# Whitespace_Daughtercard_connector.net
KiCad netlist of a schematic drawn in Altium Designer
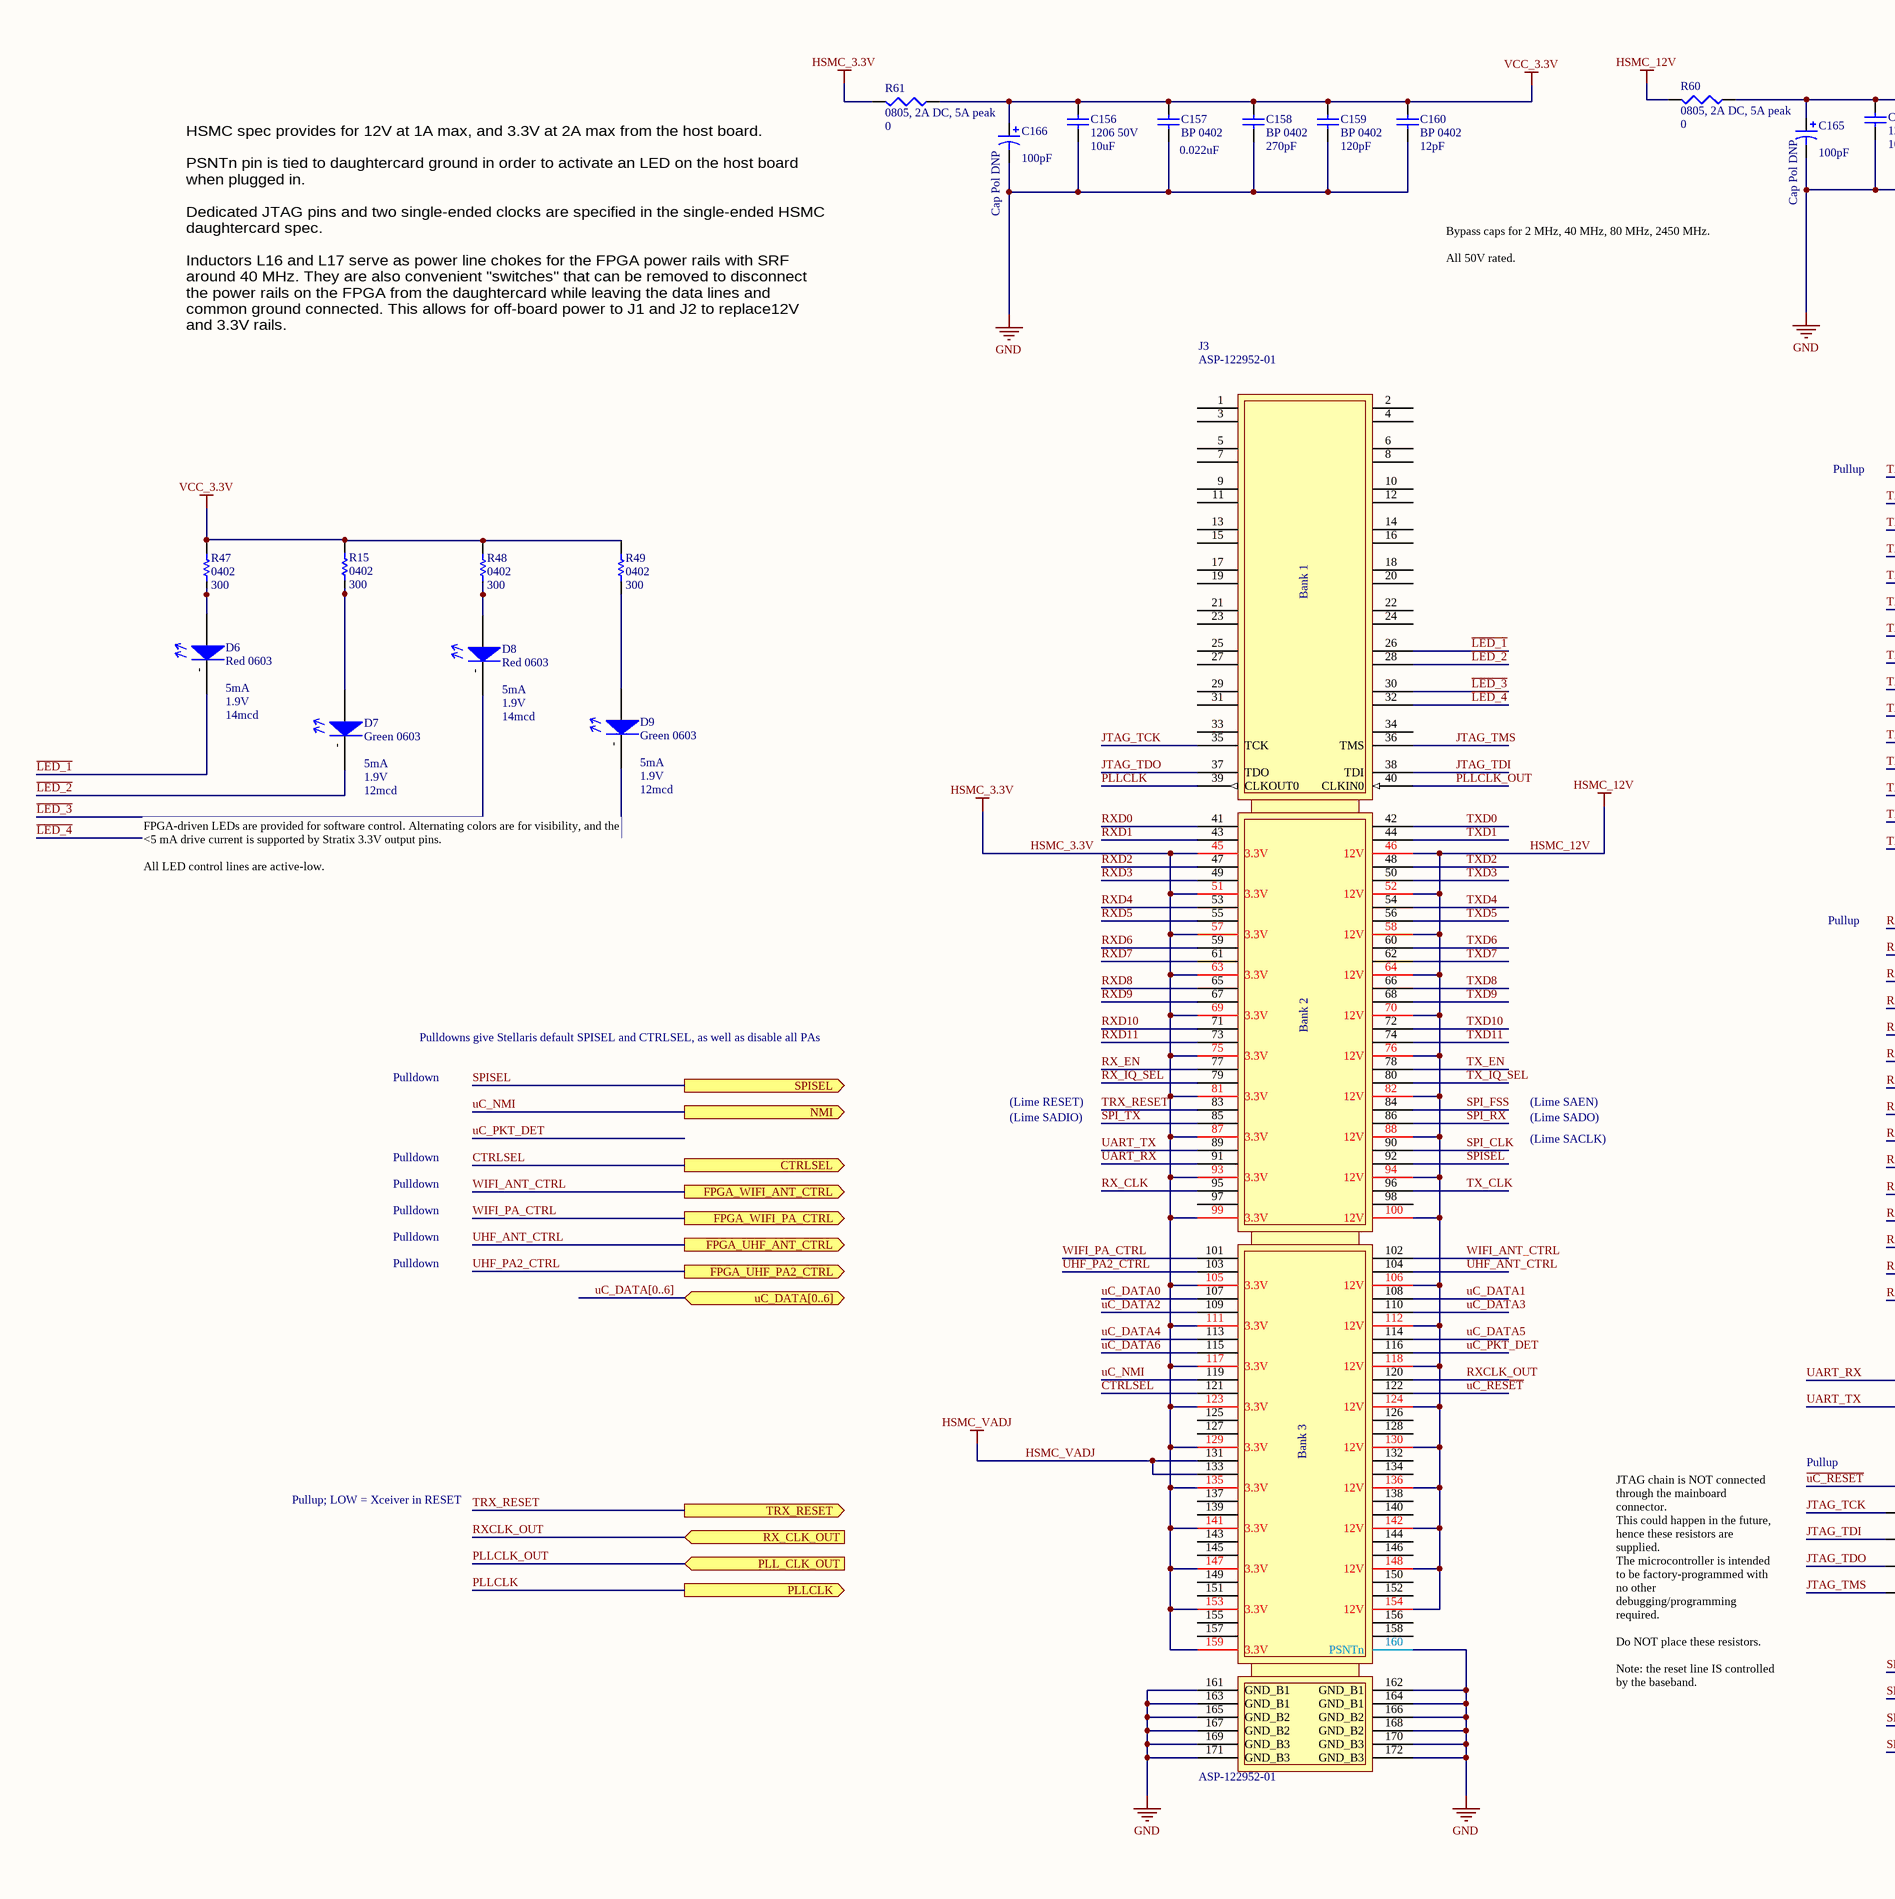
[diagram p0: Whitespace_Daughtercard_connector.SchDoc, left]
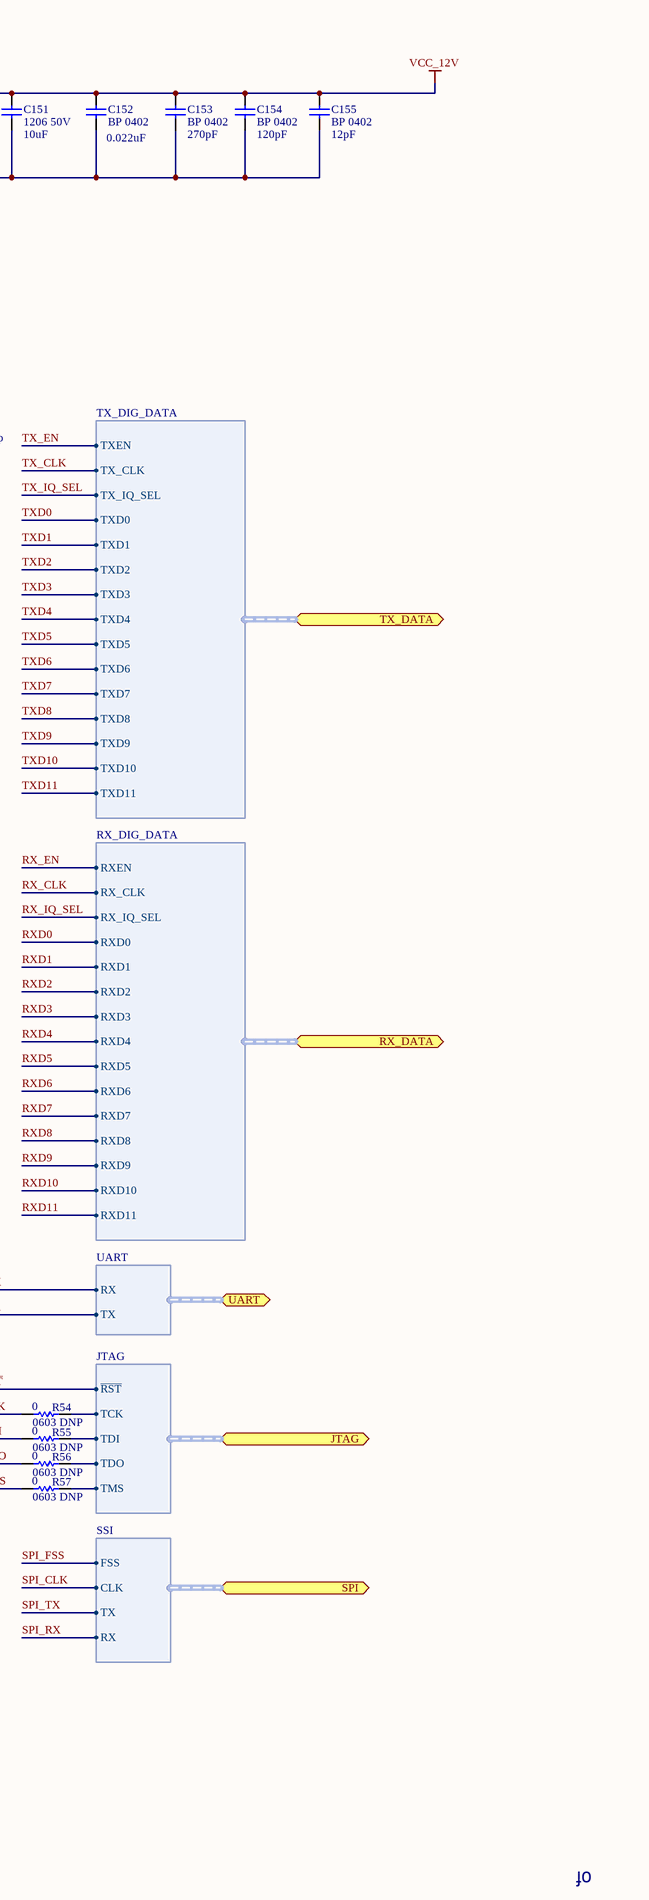
[diagram p1: Whitespace_Daughtercard_connector.SchDoc, right]

(export (version "E")
  (design (tool "Eeschema 10.0.6"))
  (components
    (comp (ref "C151")
      (value "1206 50V")
      (footprint "1206_SMT_v3")
      (description "Capacitor")
      (fields (field (name "ALTIUM_VALUE") "10uF") (field (name "PUBLISHER") "Altium Limited"))
      (libsource (lib "Miscellaneous Devices") (part "Cap"))
    )
    (comp (ref "C152")
      (value "BP 0402")
      (footprint "0402_SMT_V3")
      (description "Capacitor")
      (fields (field (name "ALTIUM_VALUE") "0.022uF") (field (name "PUBLISHER") "Altium Limited"))
      (libsource (lib "Miscellaneous Devices") (part "Cap"))
    )
    (comp (ref "C153")
      (value "BP 0402")
      (footprint "0402_SMT_v3")
      (description "Capacitor")
      (fields (field (name "ALTIUM_VALUE") "270pF") (field (name "PUBLISHER") "Altium Limited"))
      (libsource (lib "Miscellaneous Devices") (part "Cap"))
    )
    (comp (ref "C154")
      (value "BP 0402")
      (footprint "0402_SMT_v3")
      (description "Capacitor")
      (fields (field (name "ALTIUM_VALUE") "120pF") (field (name "PUBLISHER") "Altium Limited"))
      (libsource (lib "Miscellaneous Devices") (part "Cap"))
    )
    (comp (ref "C155")
      (value "BP 0402")
      (footprint "0402_SMT_v3")
      (description "Capacitor")
      (fields (field (name "ALTIUM_VALUE") "12pF") (field (name "PUBLISHER") "Altium Limited"))
      (libsource (lib "Miscellaneous Devices") (part "Cap"))
    )
    (comp (ref "C156")
      (value "1206 50V")
      (footprint "1206_SMT_v3")
      (description "Capacitor")
      (fields (field (name "ALTIUM_VALUE") "10uF") (field (name "PUBLISHER") "Altium Limited"))
      (libsource (lib "Miscellaneous Devices") (part "Cap"))
    )
    (comp (ref "C157")
      (value "BP 0402")
      (footprint "0402_SMT_V3")
      (description "Capacitor")
      (fields (field (name "ALTIUM_VALUE") "0.022uF") (field (name "PUBLISHER") "Altium Limited"))
      (libsource (lib "Miscellaneous Devices") (part "Cap"))
    )
    (comp (ref "C158")
      (value "BP 0402")
      (footprint "0402_SMT_v3")
      (description "Capacitor")
      (fields (field (name "ALTIUM_VALUE") "270pF") (field (name "PUBLISHER") "Altium Limited"))
      (libsource (lib "Miscellaneous Devices") (part "Cap"))
    )
    (comp (ref "C159")
      (value "BP 0402")
      (footprint "0402_SMT_v3")
      (description "Capacitor")
      (fields (field (name "ALTIUM_VALUE") "120pF") (field (name "PUBLISHER") "Altium Limited"))
      (libsource (lib "Miscellaneous Devices") (part "Cap"))
    )
    (comp (ref "C160")
      (value "BP 0402")
      (footprint "0402_SMT_v3")
      (description "Capacitor")
      (fields (field (name "ALTIUM_VALUE") "12pF") (field (name "PUBLISHER") "Altium Limited"))
      (libsource (lib "Miscellaneous Devices") (part "Cap"))
    )
    (comp (ref "C165")
      (value "Cap Pol DNP")
      (footprint "PANASONIC_ELEC_CAP_G_v2")
      (description "Polarized Capacitor (Surface Mount)")
      (fields (field (name "ALTIUM_VALUE") "100pF") (field (name "PUBLISHER") "Altium Limited"))
      (libsource (lib "Miscellaneous Devices") (part "Cap Pol3"))
    )
    (comp (ref "C166")
      (value "Cap Pol DNP")
      (footprint "PANASONIC_ELEC_CAP_G_v2")
      (description "Polarized Capacitor (Surface Mount)")
      (fields (field (name "ALTIUM_VALUE") "100pF") (field (name "PUBLISHER") "Altium Limited"))
      (libsource (lib "Miscellaneous Devices") (part "Cap Pol3"))
    )
    (comp (ref "D6")
      (value "Red 0603")
      (footprint "0603_POLAR")
      (fields
        (field (name "CURRENT") "5mA")
        (field (name "FORWARD VOLTAGE DROP") "1.9V")
        (field (name "LUMINOSITY") "14mcd")
      )
      (libsource (lib "RNG_Parts") (part "LED"))
    )
    (comp (ref "D7")
      (value "Green 0603")
      (footprint "0603_POLAR")
      (fields
        (field (name "CURRENT") "5mA")
        (field (name "FORWARD VOLTAGE") "1.9V")
        (field (name "LUMINOSITY") "12mcd")
      )
      (libsource (lib "RNG_Parts") (part "LED"))
    )
    (comp (ref "D8")
      (value "Red 0603")
      (footprint "0603_POLAR")
      (fields
        (field (name "CURRENT") "5mA")
        (field (name "FORWARD VOLTAGE DROP") "1.9V")
        (field (name "LUMINOSITY") "14mcd")
      )
      (libsource (lib "RNG_Parts") (part "LED"))
    )
    (comp (ref "D9")
      (value "Green 0603")
      (footprint "0603_POLAR")
      (fields
        (field (name "CURRENT") "5mA")
        (field (name "FORWARD VOLTAGE") "1.9V")
        (field (name "LUMINOSITY") "12mcd")
      )
      (libsource (lib "RNG_Parts") (part "LED"))
    )
    (comp (ref "J3")
      (value "ASP-122952-01")
      (footprint "ASP-122952-01")
      (description "Samtec HSMC Daughtercard Connector (Male)")
      (libsource (lib "RNG_Parts") (part "ASP-122952-01"))
    )
    (comp (ref "R15")
      (value "0402")
      (footprint "0402_SMT_v3")
      (description "Semiconductor Resistor")
      (fields (field (name "ALTIUM_VALUE") "300") (field (name "PUBLISHER") "Altium Limited"))
      (libsource (lib "Miscellaneous Devices") (part "Res Semi"))
    )
    (comp (ref "R47")
      (value "0402")
      (footprint "0402_SMT_v3")
      (description "Semiconductor Resistor")
      (fields (field (name "ALTIUM_VALUE") "300") (field (name "PUBLISHER") "Altium Limited"))
      (libsource (lib "Miscellaneous Devices") (part "Res Semi"))
    )
    (comp (ref "R48")
      (value "0402")
      (footprint "0402_SMT_v3")
      (description "Semiconductor Resistor")
      (fields (field (name "ALTIUM_VALUE") "300") (field (name "PUBLISHER") "Altium Limited"))
      (libsource (lib "Miscellaneous Devices") (part "Res Semi"))
    )
    (comp (ref "R49")
      (value "0402")
      (footprint "0402_SMT_v3")
      (description "Semiconductor Resistor")
      (fields (field (name "ALTIUM_VALUE") "300") (field (name "PUBLISHER") "Altium Limited"))
      (libsource (lib "Miscellaneous Devices") (part "Res Semi"))
    )
    (comp (ref "R54")
      (value "0603 DNP")
      (footprint "0603_SMT_v3")
      (description "Semiconductor Resistor")
      (fields (field (name "ALTIUM_VALUE") "0") (field (name "PUBLISHER") "Altium Limited"))
      (libsource (lib "Miscellaneous Devices") (part "Res Semi"))
    )
    (comp (ref "R55")
      (value "0603 DNP")
      (footprint "0603_SMT_v3")
      (description "Semiconductor Resistor")
      (fields (field (name "ALTIUM_VALUE") "0") (field (name "PUBLISHER") "Altium Limited"))
      (libsource (lib "Miscellaneous Devices") (part "Res Semi"))
    )
    (comp (ref "R56")
      (value "0603 DNP")
      (footprint "0603_SMT_v3")
      (description "Semiconductor Resistor")
      (fields (field (name "ALTIUM_VALUE") "0") (field (name "PUBLISHER") "Altium Limited"))
      (libsource (lib "Miscellaneous Devices") (part "Res Semi"))
    )
    (comp (ref "R57")
      (value "0603 DNP")
      (footprint "0603_SMT_v3")
      (description "Semiconductor Resistor")
      (fields (field (name "ALTIUM_VALUE") "0") (field (name "PUBLISHER") "Altium Limited"))
      (libsource (lib "Miscellaneous Devices") (part "Res Semi"))
    )
    (comp (ref "R60")
      (value "0805, 2A DC, 5A peak")
      (footprint "0805_SMT_v3")
      (description "Resistor")
      (fields (field (name "ALTIUM_VALUE") "0") (field (name "PUBLISHER") "Altium Limited"))
      (libsource (lib "Miscellaneous Devices") (part "Res3"))
    )
    (comp (ref "R61")
      (value "0805, 2A DC, 5A peak")
      (footprint "0805_SMT_v3")
      (description "Resistor")
      (fields (field (name "ALTIUM_VALUE") "0") (field (name "PUBLISHER") "Altium Limited"))
      (libsource (lib "Miscellaneous Devices") (part "Res3"))
    )
  )
  (nets
    (net (code "6") (name "/CTRLSEL") (class "Default")
      (node (ref "J3") (pin "121") (pinfunction "121_121") (pintype "passive"))
    )
    (net (code "7") (name "/JTAG_TCK") (class "Default")
      (node (ref "J3") (pin "35") (pinfunction "TCK_35") (pintype "passive"))
      (node (ref "R54") (pin "2") (pinfunction "2_2") (pintype "passive"))
    )
    (net (code "8") (name "/JTAG_TDI") (class "Default")
      (node (ref "J3") (pin "38") (pinfunction "TDI_38") (pintype "passive"))
      (node (ref "R55") (pin "2") (pinfunction "2_2") (pintype "passive"))
    )
    (net (code "9") (name "/JTAG_TDO") (class "Default")
      (node (ref "J3") (pin "37") (pinfunction "TDO_37") (pintype "passive"))
      (node (ref "R56") (pin "2") (pinfunction "2_2") (pintype "passive"))
    )
    (net (code "10") (name "/JTAG_TMS") (class "Default")
      (node (ref "J3") (pin "36") (pinfunction "TMS_36") (pintype "passive"))
      (node (ref "R57") (pin "2") (pinfunction "2_2") (pintype "passive"))
    )
    (net (code "11") (name "/LED_1") (class "Default")
      (node (ref "D6") (pin "-") (pinfunction "Cathode_-") (pintype "power_in"))
      (node (ref "J3") (pin "26") (pinfunction "26_26") (pintype "passive"))
    )
    (net (code "12") (name "/LED_2") (class "Default")
      (node (ref "D7") (pin "-") (pinfunction "Cathode_-") (pintype "power_in"))
      (node (ref "J3") (pin "28") (pinfunction "28_28") (pintype "passive"))
    )
    (net (code "13") (name "/LED_3") (class "Default")
      (node (ref "D8") (pin "-") (pinfunction "Cathode_-") (pintype "power_in"))
      (node (ref "J3") (pin "30") (pinfunction "30_30") (pintype "passive"))
    )
    (net (code "14") (name "/LED_4") (class "Default")
      (node (ref "D9") (pin "-") (pinfunction "Cathode_-") (pintype "power_in"))
      (node (ref "J3") (pin "32") (pinfunction "32_32") (pintype "passive"))
    )
    (net (code "15") (name "/PLLCLK") (class "Default")
      (node (ref "J3") (pin "39") (pinfunction "CLKOUT0_39") (pintype "output"))
    )
    (net (code "16") (name "/PLLCLK_OUT") (class "Default")
      (node (ref "J3") (pin "40") (pinfunction "CLKIN0_40") (pintype "input"))
    )
    (net (code "17") (name "/RXCLK_OUT") (class "Default")
      (node (ref "J3") (pin "120") (pinfunction "120_120") (pintype "passive"))
    )
    (net (code "18") (name "/RXD0") (class "Default")
      (node (ref "J3") (pin "41") (pinfunction "41_41") (pintype "passive"))
    )
    (net (code "19") (name "/RXD1") (class "Default")
      (node (ref "J3") (pin "43") (pinfunction "43_43") (pintype "passive"))
    )
    (net (code "20") (name "/RXD2") (class "Default")
      (node (ref "J3") (pin "47") (pinfunction "47_47") (pintype "passive"))
    )
    (net (code "21") (name "/RXD3") (class "Default")
      (node (ref "J3") (pin "49") (pinfunction "49_49") (pintype "passive"))
    )
    (net (code "22") (name "/RXD4") (class "Default")
      (node (ref "J3") (pin "53") (pinfunction "53_53") (pintype "passive"))
    )
    (net (code "23") (name "/RXD5") (class "Default")
      (node (ref "J3") (pin "55") (pinfunction "55_55") (pintype "passive"))
    )
    (net (code "24") (name "/RXD6") (class "Default")
      (node (ref "J3") (pin "59") (pinfunction "59_59") (pintype "passive"))
    )
    (net (code "25") (name "/RXD7") (class "Default")
      (node (ref "J3") (pin "61") (pinfunction "61_61") (pintype "passive"))
    )
    (net (code "26") (name "/RXD8") (class "Default")
      (node (ref "J3") (pin "65") (pinfunction "65_65") (pintype "passive"))
    )
    (net (code "27") (name "/RXD9") (class "Default")
      (node (ref "J3") (pin "67") (pinfunction "67_67") (pintype "passive"))
    )
    (net (code "28") (name "/RXD10") (class "Default")
      (node (ref "J3") (pin "71") (pinfunction "71_71") (pintype "passive"))
    )
    (net (code "29") (name "/RXD11") (class "Default")
      (node (ref "J3") (pin "73") (pinfunction "73_73") (pintype "passive"))
    )
    (net (code "30") (name "/RX_CLK") (class "Default")
      (node (ref "J3") (pin "95") (pinfunction "95_95") (pintype "passive"))
    )
    (net (code "31") (name "/RX_EN") (class "Default")
      (node (ref "J3") (pin "77") (pinfunction "77_77") (pintype "passive"))
    )
    (net (code "32") (name "/RX_IQ_SEL") (class "Default")
      (node (ref "J3") (pin "79") (pinfunction "79_79") (pintype "passive"))
    )
    (net (code "33") (name "/SPISEL") (class "Default")
      (node (ref "J3") (pin "92") (pinfunction "92_92") (pintype "passive"))
    )
    (net (code "34") (name "/SPI_CLK") (class "Default")
      (node (ref "J3") (pin "90") (pinfunction "90_90") (pintype "passive"))
    )
    (net (code "35") (name "/SPI_FSS") (class "Default")
      (node (ref "J3") (pin "84") (pinfunction "84_84") (pintype "passive"))
    )
    (net (code "36") (name "/SPI_RX") (class "Default")
      (node (ref "J3") (pin "86") (pinfunction "86_86") (pintype "passive"))
    )
    (net (code "37") (name "/SPI_TX") (class "Default")
      (node (ref "J3") (pin "85") (pinfunction "85_85") (pintype "passive"))
    )
    (net (code "38") (name "/TCK") (class "Default")
      (node (ref "R54") (pin "1") (pinfunction "1_1") (pintype "passive"))
    )
    (net (code "39") (name "/TDI") (class "Default")
      (node (ref "R55") (pin "1") (pinfunction "1_1") (pintype "passive"))
    )
    (net (code "40") (name "/TDO") (class "Default")
      (node (ref "R56") (pin "1") (pinfunction "1_1") (pintype "passive"))
    )
    (net (code "41") (name "/TMS") (class "Default")
      (node (ref "R57") (pin "1") (pinfunction "1_1") (pintype "passive"))
    )
    (net (code "42") (name "/TRX_RESET") (class "Default")
      (node (ref "J3") (pin "83") (pinfunction "83_83") (pintype "passive"))
    )
    (net (code "43") (name "/TXD0") (class "Default")
      (node (ref "J3") (pin "42") (pinfunction "42_42") (pintype "passive"))
    )
    (net (code "44") (name "/TXD1") (class "Default")
      (node (ref "J3") (pin "44") (pinfunction "44_44") (pintype "passive"))
    )
    (net (code "45") (name "/TXD2") (class "Default")
      (node (ref "J3") (pin "48") (pinfunction "48_48") (pintype "passive"))
    )
    (net (code "46") (name "/TXD3") (class "Default")
      (node (ref "J3") (pin "50") (pinfunction "50_50") (pintype "passive"))
    )
    (net (code "47") (name "/TXD4") (class "Default")
      (node (ref "J3") (pin "54") (pinfunction "54_54") (pintype "passive"))
    )
    (net (code "48") (name "/TXD5") (class "Default")
      (node (ref "J3") (pin "56") (pinfunction "56_56") (pintype "passive"))
    )
    (net (code "49") (name "/TXD6") (class "Default")
      (node (ref "J3") (pin "60") (pinfunction "60_60") (pintype "passive"))
    )
    (net (code "50") (name "/TXD7") (class "Default")
      (node (ref "J3") (pin "62") (pinfunction "62_62") (pintype "passive"))
    )
    (net (code "51") (name "/TXD8") (class "Default")
      (node (ref "J3") (pin "66") (pinfunction "66_66") (pintype "passive"))
    )
    (net (code "52") (name "/TXD9") (class "Default")
      (node (ref "J3") (pin "68") (pinfunction "68_68") (pintype "passive"))
    )
    (net (code "53") (name "/TXD10") (class "Default")
      (node (ref "J3") (pin "72") (pinfunction "72_72") (pintype "passive"))
    )
    (net (code "54") (name "/TXD11") (class "Default")
      (node (ref "J3") (pin "74") (pinfunction "74_74") (pintype "passive"))
    )
    (net (code "55") (name "/TX_CLK") (class "Default")
      (node (ref "J3") (pin "96") (pinfunction "96_96") (pintype "passive"))
    )
    (net (code "56") (name "/TX_EN") (class "Default")
      (node (ref "J3") (pin "78") (pinfunction "78_78") (pintype "passive"))
    )
    (net (code "57") (name "/TX_IQ_SEL") (class "Default")
      (node (ref "J3") (pin "80") (pinfunction "80_80") (pintype "passive"))
    )
    (net (code "58") (name "/UART_RX") (class "Default")
      (node (ref "J3") (pin "91") (pinfunction "91_91") (pintype "passive"))
    )
    (net (code "59") (name "/UART_TX") (class "Default")
      (node (ref "J3") (pin "89") (pinfunction "89_89") (pintype "passive"))
    )
    (net (code "60") (name "/UHF_ANT_CTRL") (class "Default")
      (node (ref "J3") (pin "104") (pinfunction "104_104") (pintype "passive"))
    )
    (net (code "61") (name "/UHF_PA2_CTRL") (class "Default")
      (node (ref "J3") (pin "103") (pinfunction "103_103") (pintype "passive"))
    )
    (net (code "62") (name "/WIFI_ANT_CTRL") (class "Default")
      (node (ref "J3") (pin "102") (pinfunction "102_102") (pintype "passive"))
    )
    (net (code "63") (name "/WIFI_PA_CTRL") (class "Default")
      (node (ref "J3") (pin "101") (pinfunction "101_101") (pintype "passive"))
    )
    (net (code "64") (name "/uC_DATA0") (class "Default")
      (node (ref "J3") (pin "107") (pinfunction "107_107") (pintype "passive"))
    )
    (net (code "65") (name "/uC_DATA1") (class "Default")
      (node (ref "J3") (pin "108") (pinfunction "108_108") (pintype "passive"))
    )
    (net (code "66") (name "/uC_DATA2") (class "Default")
      (node (ref "J3") (pin "109") (pinfunction "109_109") (pintype "passive"))
    )
    (net (code "67") (name "/uC_DATA3") (class "Default")
      (node (ref "J3") (pin "110") (pinfunction "110_110") (pintype "passive"))
    )
    (net (code "68") (name "/uC_DATA4") (class "Default")
      (node (ref "J3") (pin "113") (pinfunction "113_113") (pintype "passive"))
    )
    (net (code "69") (name "/uC_DATA5") (class "Default")
      (node (ref "J3") (pin "114") (pinfunction "114_114") (pintype "passive"))
    )
    (net (code "70") (name "/uC_DATA6") (class "Default")
      (node (ref "J3") (pin "115") (pinfunction "115_115") (pintype "passive"))
    )
    (net (code "72") (name "/uC_NMI") (class "Default")
      (node (ref "J3") (pin "119") (pinfunction "119_119") (pintype "passive"))
    )
    (net (code "73") (name "/uC_PKT_DET") (class "Default")
      (node (ref "J3") (pin "116") (pinfunction "116_116") (pintype "passive"))
    )
    (net (code "74") (name "/uC_RESET") (class "Default")
      (node (ref "J3") (pin "122") (pinfunction "122_122") (pintype "passive"))
    )
    (net (code "80") (name "GND") (class "Default")
      (node (ref "C151") (pin "1") (pinfunction "1_1") (pintype "passive"))
      (node (ref "C152") (pin "1") (pinfunction "1_1") (pintype "passive"))
      (node (ref "C153") (pin "2") (pinfunction "2_2") (pintype "passive"))
      (node (ref "C154") (pin "1") (pinfunction "1_1") (pintype "passive"))
      (node (ref "C155") (pin "2") (pinfunction "2_2") (pintype "passive"))
      (node (ref "C156") (pin "1") (pinfunction "1_1") (pintype "passive"))
      (node (ref "C157") (pin "1") (pinfunction "1_1") (pintype "passive"))
      (node (ref "C158") (pin "2") (pinfunction "2_2") (pintype "passive"))
      (node (ref "C159") (pin "1") (pinfunction "1_1") (pintype "passive"))
      (node (ref "C160") (pin "2") (pinfunction "2_2") (pintype "passive"))
      (node (ref "C165") (pin "2") (pinfunction "2_2") (pintype "passive"))
      (node (ref "C166") (pin "2") (pinfunction "2_2") (pintype "passive"))
      (node (ref "J3") (pin "160") (pinfunction "PSNTn_160") (pintype "power_in"))
      (node (ref "J3") (pin "161") (pinfunction "GND_B1_161") (pintype "power_in"))
      (node (ref "J3") (pin "162") (pinfunction "GND_B1_162") (pintype "power_in"))
      (node (ref "J3") (pin "163") (pinfunction "GND_B1_163") (pintype "power_in"))
      (node (ref "J3") (pin "164") (pinfunction "GND_B1_164") (pintype "power_in"))
      (node (ref "J3") (pin "165") (pinfunction "GND_B2_165") (pintype "power_in"))
      (node (ref "J3") (pin "166") (pinfunction "GND_B2_166") (pintype "power_in"))
      (node (ref "J3") (pin "167") (pinfunction "GND_B2_167") (pintype "power_in"))
      (node (ref "J3") (pin "168") (pinfunction "GND_B2_168") (pintype "power_in"))
      (node (ref "J3") (pin "169") (pinfunction "GND_B3_169") (pintype "power_in"))
      (node (ref "J3") (pin "170") (pinfunction "GND_B3_170") (pintype "power_in"))
      (node (ref "J3") (pin "171") (pinfunction "GND_B3_171") (pintype "power_in"))
      (node (ref "J3") (pin "172") (pinfunction "GND_B3_172") (pintype "power_in"))
    )
    (net (code "81") (name "HSMC_3.3V") (class "Default")
      (node (ref "J3") (pin "105") (pinfunction "3.3V_105") (pintype "power_in"))
      (node (ref "J3") (pin "111") (pinfunction "3.3V_111") (pintype "power_in"))
      (node (ref "J3") (pin "117") (pinfunction "3.3V_117") (pintype "power_in"))
      (node (ref "J3") (pin "123") (pinfunction "3.3V_123") (pintype "power_in"))
      (node (ref "J3") (pin "129") (pinfunction "3.3V_129") (pintype "power_in"))
      (node (ref "J3") (pin "135") (pinfunction "3.3V_135") (pintype "power_in"))
      (node (ref "J3") (pin "141") (pinfunction "3.3V_141") (pintype "power_in"))
      (node (ref "J3") (pin "147") (pinfunction "3.3V_147") (pintype "power_in"))
      (node (ref "J3") (pin "153") (pinfunction "3.3V_153") (pintype "power_in"))
      (node (ref "J3") (pin "159") (pinfunction "3.3V_159") (pintype "power_in"))
      (node (ref "J3") (pin "45") (pinfunction "3.3V_45") (pintype "power_in"))
      (node (ref "J3") (pin "51") (pinfunction "3.3V_51") (pintype "power_in"))
      (node (ref "J3") (pin "57") (pinfunction "3.3V_57") (pintype "power_in"))
      (node (ref "J3") (pin "63") (pinfunction "3.3V_63") (pintype "power_in"))
      (node (ref "J3") (pin "69") (pinfunction "3.3V_69") (pintype "power_in"))
      (node (ref "J3") (pin "75") (pinfunction "3.3V_75") (pintype "power_in"))
      (node (ref "J3") (pin "81") (pinfunction "3.3V_81") (pintype "power_in"))
      (node (ref "J3") (pin "87") (pinfunction "3.3V_87") (pintype "power_in"))
      (node (ref "J3") (pin "93") (pinfunction "3.3V_93") (pintype "power_in"))
      (node (ref "J3") (pin "99") (pinfunction "3.3V_99") (pintype "power_in"))
      (node (ref "R61") (pin "2") (pinfunction "2_2") (pintype "passive"))
    )
    (net (code "82") (name "HSMC_12V") (class "Default")
      (node (ref "J3") (pin "100") (pinfunction "12V_100") (pintype "power_in"))
      (node (ref "J3") (pin "106") (pinfunction "12V_106") (pintype "power_in"))
      (node (ref "J3") (pin "112") (pinfunction "12V_112") (pintype "power_in"))
      (node (ref "J3") (pin "118") (pinfunction "12V_118") (pintype "power_in"))
      (node (ref "J3") (pin "124") (pinfunction "12V_124") (pintype "power_in"))
      (node (ref "J3") (pin "130") (pinfunction "12V_130") (pintype "power_in"))
      (node (ref "J3") (pin "136") (pinfunction "12V_136") (pintype "power_in"))
      (node (ref "J3") (pin "142") (pinfunction "12V_142") (pintype "power_in"))
      (node (ref "J3") (pin "148") (pinfunction "12V_148") (pintype "power_in"))
      (node (ref "J3") (pin "154") (pinfunction "12V_154") (pintype "power_in"))
      (node (ref "J3") (pin "46") (pinfunction "12V_46") (pintype "power_in"))
      (node (ref "J3") (pin "52") (pinfunction "12V_52") (pintype "power_in"))
      (node (ref "J3") (pin "58") (pinfunction "12V_58") (pintype "power_in"))
      (node (ref "J3") (pin "64") (pinfunction "12V_64") (pintype "power_in"))
      (node (ref "J3") (pin "70") (pinfunction "12V_70") (pintype "power_in"))
      (node (ref "J3") (pin "76") (pinfunction "12V_76") (pintype "power_in"))
      (node (ref "J3") (pin "82") (pinfunction "12V_82") (pintype "power_in"))
      (node (ref "J3") (pin "88") (pinfunction "12V_88") (pintype "power_in"))
      (node (ref "J3") (pin "94") (pinfunction "12V_94") (pintype "power_in"))
      (node (ref "R60") (pin "2") (pinfunction "2_2") (pintype "passive"))
    )
    (net (code "83") (name "HSMC_VADJ") (class "Default")
      (node (ref "J3") (pin "131") (pinfunction "131_131") (pintype "passive"))
      (node (ref "J3") (pin "133") (pinfunction "133_133") (pintype "passive"))
    )
    (net (code "84") (name "Net-(D6-Anode)") (class "Default")
      (node (ref "D6") (pin "+") (pinfunction "Anode_+") (pintype "power_in"))
      (node (ref "R47") (pin "2") (pinfunction "2_2") (pintype "passive"))
    )
    (net (code "85") (name "Net-(D7-Anode)") (class "Default")
      (node (ref "D7") (pin "+") (pinfunction "Anode_+") (pintype "power_in"))
      (node (ref "R15") (pin "2") (pinfunction "2_2") (pintype "passive"))
    )
    (net (code "86") (name "Net-(D8-Anode)") (class "Default")
      (node (ref "D8") (pin "+") (pinfunction "Anode_+") (pintype "power_in"))
      (node (ref "R48") (pin "2") (pinfunction "2_2") (pintype "passive"))
    )
    (net (code "87") (name "Net-(D9-Anode)") (class "Default")
      (node (ref "D9") (pin "+") (pinfunction "Anode_+") (pintype "power_in"))
      (node (ref "R49") (pin "2") (pinfunction "2_2") (pintype "passive"))
    )
    (net (code "88") (name "VCC_3.3V") (class "Default")
      (node (ref "C156") (pin "2") (pinfunction "2_2") (pintype "passive"))
      (node (ref "C157") (pin "2") (pinfunction "2_2") (pintype "passive"))
      (node (ref "C158") (pin "1") (pinfunction "1_1") (pintype "passive"))
      (node (ref "C159") (pin "2") (pinfunction "2_2") (pintype "passive"))
      (node (ref "C160") (pin "1") (pinfunction "1_1") (pintype "passive"))
      (node (ref "C166") (pin "1") (pinfunction "1_1") (pintype "passive"))
      (node (ref "R15") (pin "1") (pinfunction "1_1") (pintype "passive"))
      (node (ref "R47") (pin "1") (pinfunction "1_1") (pintype "passive"))
      (node (ref "R48") (pin "1") (pinfunction "1_1") (pintype "passive"))
      (node (ref "R49") (pin "1") (pinfunction "1_1") (pintype "passive"))
      (node (ref "R61") (pin "1") (pinfunction "1_1") (pintype "passive"))
    )
    (net (code "89") (name "VCC_12V") (class "Default")
      (node (ref "C151") (pin "2") (pinfunction "2_2") (pintype "passive"))
      (node (ref "C152") (pin "2") (pinfunction "2_2") (pintype "passive"))
      (node (ref "C153") (pin "1") (pinfunction "1_1") (pintype "passive"))
      (node (ref "C154") (pin "2") (pinfunction "2_2") (pintype "passive"))
      (node (ref "C155") (pin "1") (pinfunction "1_1") (pintype "passive"))
      (node (ref "C165") (pin "1") (pinfunction "1_1") (pintype "passive"))
      (node (ref "R60") (pin "1") (pinfunction "1_1") (pintype "passive"))
    )
    (net (code "90") (name "unconnected-(J3-Pad1)") (class "Default")
      (node (ref "J3") (pin "1") (pinfunction "1_1") (pintype "passive"))
    )
    (net (code "91") (name "unconnected-(J3-Pad2)") (class "Default")
      (node (ref "J3") (pin "2") (pinfunction "2_2") (pintype "passive"))
    )
    (net (code "92") (name "unconnected-(J3-Pad3)") (class "Default")
      (node (ref "J3") (pin "3") (pinfunction "3_3") (pintype "passive"))
    )
    (net (code "93") (name "unconnected-(J3-Pad4)") (class "Default")
      (node (ref "J3") (pin "4") (pinfunction "4_4") (pintype "passive"))
    )
    (net (code "94") (name "unconnected-(J3-Pad5)") (class "Default")
      (node (ref "J3") (pin "5") (pinfunction "5_5") (pintype "passive"))
    )
    (net (code "95") (name "unconnected-(J3-Pad6)") (class "Default")
      (node (ref "J3") (pin "6") (pinfunction "6_6") (pintype "passive"))
    )
    (net (code "96") (name "unconnected-(J3-Pad7)") (class "Default")
      (node (ref "J3") (pin "7") (pinfunction "7_7") (pintype "passive"))
    )
    (net (code "97") (name "unconnected-(J3-Pad8)") (class "Default")
      (node (ref "J3") (pin "8") (pinfunction "8_8") (pintype "passive"))
    )
    (net (code "98") (name "unconnected-(J3-Pad9)") (class "Default")
      (node (ref "J3") (pin "9") (pinfunction "9_9") (pintype "passive"))
    )
    (net (code "99") (name "unconnected-(J3-Pad10)") (class "Default")
      (node (ref "J3") (pin "10") (pinfunction "10_10") (pintype "passive"))
    )
    (net (code "100") (name "unconnected-(J3-Pad11)") (class "Default")
      (node (ref "J3") (pin "11") (pinfunction "11_11") (pintype "passive"))
    )
    (net (code "101") (name "unconnected-(J3-Pad12)") (class "Default")
      (node (ref "J3") (pin "12") (pinfunction "12_12") (pintype "passive"))
    )
    (net (code "102") (name "unconnected-(J3-Pad13)") (class "Default")
      (node (ref "J3") (pin "13") (pinfunction "13_13") (pintype "passive"))
    )
    (net (code "103") (name "unconnected-(J3-Pad14)") (class "Default")
      (node (ref "J3") (pin "14") (pinfunction "14_14") (pintype "passive"))
    )
    (net (code "104") (name "unconnected-(J3-Pad15)") (class "Default")
      (node (ref "J3") (pin "15") (pinfunction "15_15") (pintype "passive"))
    )
    (net (code "105") (name "unconnected-(J3-Pad16)") (class "Default")
      (node (ref "J3") (pin "16") (pinfunction "16_16") (pintype "passive"))
    )
    (net (code "106") (name "unconnected-(J3-Pad17)") (class "Default")
      (node (ref "J3") (pin "17") (pinfunction "17_17") (pintype "passive"))
    )
    (net (code "107") (name "unconnected-(J3-Pad18)") (class "Default")
      (node (ref "J3") (pin "18") (pinfunction "18_18") (pintype "passive"))
    )
    (net (code "108") (name "unconnected-(J3-Pad19)") (class "Default")
      (node (ref "J3") (pin "19") (pinfunction "19_19") (pintype "passive"))
    )
    (net (code "109") (name "unconnected-(J3-Pad20)") (class "Default")
      (node (ref "J3") (pin "20") (pinfunction "20_20") (pintype "passive"))
    )
    (net (code "110") (name "unconnected-(J3-Pad21)") (class "Default")
      (node (ref "J3") (pin "21") (pinfunction "21_21") (pintype "passive"))
    )
    (net (code "111") (name "unconnected-(J3-Pad22)") (class "Default")
      (node (ref "J3") (pin "22") (pinfunction "22_22") (pintype "passive"))
    )
    (net (code "112") (name "unconnected-(J3-Pad23)") (class "Default")
      (node (ref "J3") (pin "23") (pinfunction "23_23") (pintype "passive"))
    )
    (net (code "113") (name "unconnected-(J3-Pad24)") (class "Default")
      (node (ref "J3") (pin "24") (pinfunction "24_24") (pintype "passive"))
    )
    (net (code "114") (name "unconnected-(J3-Pad25)") (class "Default")
      (node (ref "J3") (pin "25") (pinfunction "25_25") (pintype "passive"))
    )
    (net (code "115") (name "unconnected-(J3-Pad27)") (class "Default")
      (node (ref "J3") (pin "27") (pinfunction "27_27") (pintype "passive"))
    )
    (net (code "116") (name "unconnected-(J3-Pad29)") (class "Default")
      (node (ref "J3") (pin "29") (pinfunction "29_29") (pintype "passive"))
    )
    (net (code "117") (name "unconnected-(J3-Pad31)") (class "Default")
      (node (ref "J3") (pin "31") (pinfunction "31_31") (pintype "passive"))
    )
    (net (code "118") (name "unconnected-(J3-Pad97)") (class "Default")
      (node (ref "J3") (pin "97") (pinfunction "97_97") (pintype "passive"))
    )
    (net (code "119") (name "unconnected-(J3-Pad98)") (class "Default")
      (node (ref "J3") (pin "98") (pinfunction "98_98") (pintype "passive"))
    )
    (net (code "120") (name "unconnected-(J3-Pad125)") (class "Default")
      (node (ref "J3") (pin "125") (pinfunction "125_125") (pintype "passive"))
    )
    (net (code "121") (name "unconnected-(J3-Pad126)") (class "Default")
      (node (ref "J3") (pin "126") (pinfunction "126_126") (pintype "passive"))
    )
    (net (code "122") (name "unconnected-(J3-Pad127)") (class "Default")
      (node (ref "J3") (pin "127") (pinfunction "127_127") (pintype "passive"))
    )
    (net (code "123") (name "unconnected-(J3-Pad128)") (class "Default")
      (node (ref "J3") (pin "128") (pinfunction "128_128") (pintype "passive"))
    )
    (net (code "124") (name "unconnected-(J3-Pad132)") (class "Default")
      (node (ref "J3") (pin "132") (pinfunction "132_132") (pintype "passive"))
    )
    (net (code "125") (name "unconnected-(J3-Pad134)") (class "Default")
      (node (ref "J3") (pin "134") (pinfunction "134_134") (pintype "passive"))
    )
    (net (code "126") (name "unconnected-(J3-Pad137)") (class "Default")
      (node (ref "J3") (pin "137") (pinfunction "137_137") (pintype "passive"))
    )
    (net (code "127") (name "unconnected-(J3-Pad138)") (class "Default")
      (node (ref "J3") (pin "138") (pinfunction "138_138") (pintype "passive"))
    )
    (net (code "128") (name "unconnected-(J3-Pad139)") (class "Default")
      (node (ref "J3") (pin "139") (pinfunction "139_139") (pintype "passive"))
    )
    (net (code "129") (name "unconnected-(J3-Pad140)") (class "Default")
      (node (ref "J3") (pin "140") (pinfunction "140_140") (pintype "passive"))
    )
    (net (code "130") (name "unconnected-(J3-Pad143)") (class "Default")
      (node (ref "J3") (pin "143") (pinfunction "143_143") (pintype "passive"))
    )
    (net (code "131") (name "unconnected-(J3-Pad144)") (class "Default")
      (node (ref "J3") (pin "144") (pinfunction "144_144") (pintype "passive"))
    )
    (net (code "132") (name "unconnected-(J3-Pad145)") (class "Default")
      (node (ref "J3") (pin "145") (pinfunction "145_145") (pintype "passive"))
    )
    (net (code "133") (name "unconnected-(J3-Pad146)") (class "Default")
      (node (ref "J3") (pin "146") (pinfunction "146_146") (pintype "passive"))
    )
    (net (code "134") (name "unconnected-(J3-Pad149)") (class "Default")
      (node (ref "J3") (pin "149") (pinfunction "149_149") (pintype "passive"))
    )
    (net (code "135") (name "unconnected-(J3-Pad150)") (class "Default")
      (node (ref "J3") (pin "150") (pinfunction "150_150") (pintype "passive"))
    )
    (net (code "136") (name "unconnected-(J3-Pad151)") (class "Default")
      (node (ref "J3") (pin "151") (pinfunction "151_151") (pintype "passive"))
    )
    (net (code "137") (name "unconnected-(J3-Pad152)") (class "Default")
      (node (ref "J3") (pin "152") (pinfunction "152_152") (pintype "passive"))
    )
    (net (code "138") (name "unconnected-(J3-Pad155)") (class "Default")
      (node (ref "J3") (pin "155") (pinfunction "155_155") (pintype "passive"))
    )
    (net (code "139") (name "unconnected-(J3-Pad156)") (class "Default")
      (node (ref "J3") (pin "156") (pinfunction "156_156") (pintype "passive"))
    )
    (net (code "140") (name "unconnected-(J3-Pad157)") (class "Default")
      (node (ref "J3") (pin "157") (pinfunction "157_157") (pintype "passive"))
    )
    (net (code "141") (name "unconnected-(J3-Pad158)") (class "Default")
      (node (ref "J3") (pin "158") (pinfunction "158_158") (pintype "passive"))
    )
    (net (code "142") (name "unconnected-(J3-SCL-Pad34)") (class "Default")
      (node (ref "J3") (pin "34") (pinfunction "SCL_34") (pintype "passive"))
    )
    (net (code "143") (name "unconnected-(J3-SDA-Pad33)") (class "Default")
      (node (ref "J3") (pin "33") (pinfunction "SDA_33") (pintype "passive"))
    )
  )
)
